# vertical_counter.net
KiCad netlist of a schematic drawn in Altium Designer
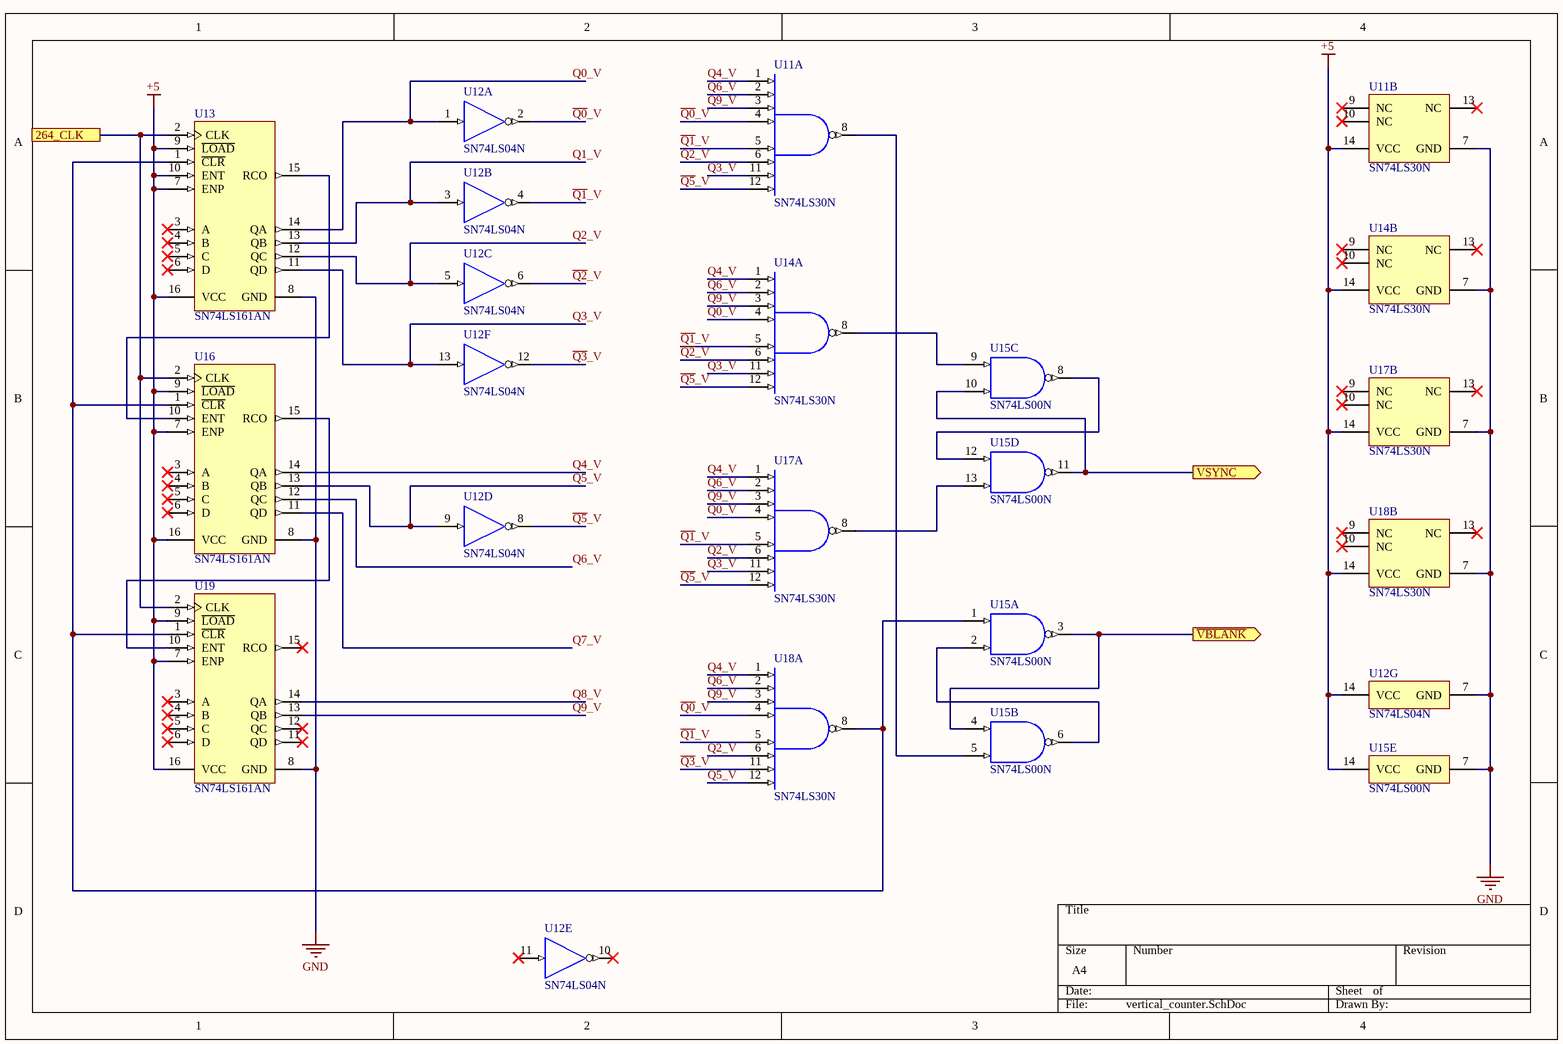
[diagram p0: vertical_counter.SchDoc]

(export (version "E")
  (design (tool "Eeschema 10.0.6"))
  (components
    (comp (ref "U11")
      (value "SN74LS30N")
      (footprint "N0014A")
      (description "8-input positive-NAND gates, N0014A, TUBE")
      (fields
        (field (name "GENERIC PART NUMBER") "SN74LS30")
        (field (name "MANUFACTURER") "Texas Instruments")
      )
      (libsource (lib "Altium Content Vault") (part "TI-SN74XX30-D0014A-14"))
    )
    (comp (ref "U12")
      (value "SN74LS04N")
      (footprint "N0014A")
      (description "Hex inverters, N0014A, TUBE")
      (fields
        (field (name "MANUFACTURER") "Texas Instruments")
        (field (name "GENERIC PART NUMBER") "SN74LS04")
      )
      (libsource (lib "Altium Content Vault") (part "TI-CD_SNX4XXXXXX4X_19A-14"))
    )
    (comp (ref "U13")
      (value "SN74LS161AN")
      (footprint "N0016A")
      (description "Synchronous 4-Bit Binary Counters, N0016A, TUBE")
      (fields
        (field (name "GENERIC PART NUMBER") "SN74LS161A")
        (field (name "MANUFACTURER") "Texas Instruments")
      )
      (libsource (lib "Altium Content Vault") (part "TI-CD_SNX4XXX161_163X-16"))
    )
    (comp (ref "U14")
      (value "SN74LS30N")
      (footprint "N0014A")
      (description "8-input positive-NAND gates, N0014A, TUBE")
      (fields
        (field (name "GENERIC PART NUMBER") "SN74LS30")
        (field (name "MANUFACTURER") "Texas Instruments")
      )
      (libsource (lib "Altium Content Vault") (part "TI-SN74XX30-D0014A-14"))
    )
    (comp (ref "U15")
      (value "SN74LS00N")
      (footprint "N0014A")
      (description "Quad 2-input positive-NAND gates, N0014A, TUBE")
      (fields
        (field (name "MANUFACTURER") "Texas Instruments")
        (field (name "GENERIC PART NUMBER") "SN74LS00")
      )
      (libsource (lib "Altium Content Vault") (part "TI-NAND-4-2IN-14_G"))
    )
    (comp (ref "U16")
      (value "SN74LS161AN")
      (footprint "N0016A")
      (description "Synchronous 4-Bit Binary Counters, N0016A, TUBE")
      (fields
        (field (name "GENERIC PART NUMBER") "SN74LS161A")
        (field (name "MANUFACTURER") "Texas Instruments")
      )
      (libsource (lib "Altium Content Vault") (part "TI-CD_SNX4XXX161_163X-16"))
    )
    (comp (ref "U17")
      (value "SN74LS30N")
      (footprint "N0014A")
      (description "8-input positive-NAND gates, N0014A, TUBE")
      (fields
        (field (name "GENERIC PART NUMBER") "SN74LS30")
        (field (name "MANUFACTURER") "Texas Instruments")
      )
      (libsource (lib "Altium Content Vault") (part "TI-SN74XX30-D0014A-14"))
    )
    (comp (ref "U18")
      (value "SN74LS30N")
      (footprint "N0014A")
      (description "8-input positive-NAND gates, N0014A, TUBE")
      (fields
        (field (name "GENERIC PART NUMBER") "SN74LS30")
        (field (name "MANUFACTURER") "Texas Instruments")
      )
      (libsource (lib "Altium Content Vault") (part "TI-SN74XX30-D0014A-14"))
    )
    (comp (ref "U19")
      (value "SN74LS161AN")
      (footprint "N0016A")
      (description "Synchronous 4-Bit Binary Counters, N0016A, TUBE")
      (fields
        (field (name "GENERIC PART NUMBER") "SN74LS161A")
        (field (name "MANUFACTURER") "Texas Instruments")
      )
      (libsource (lib "Altium Content Vault") (part "TI-CD_SNX4XXX161_163X-16"))
    )
  )
  (nets
    (net (code "1") (name "+5") (class "Default")
      (node (ref "U11") (pin "14") (pinfunction "VCC_14") (pintype "power_in"))
      (node (ref "U12") (pin "14") (pinfunction "VCC_14") (pintype "power_in"))
      (node (ref "U13") (pin "10") (pinfunction "ENT_10") (pintype "input"))
      (node (ref "U13") (pin "16") (pinfunction "VCC_16") (pintype "power_in"))
      (node (ref "U13") (pin "7") (pinfunction "ENP_7") (pintype "input"))
      (node (ref "U13") (pin "9") (pinfunction "~{LOAD}_9") (pintype "input"))
      (node (ref "U14") (pin "14") (pinfunction "VCC_14") (pintype "power_in"))
      (node (ref "U15") (pin "14") (pinfunction "VCC_14") (pintype "power_in"))
      (node (ref "U16") (pin "16") (pinfunction "VCC_16") (pintype "power_in"))
      (node (ref "U16") (pin "7") (pinfunction "ENP_7") (pintype "input"))
      (node (ref "U16") (pin "9") (pinfunction "~{LOAD}_9") (pintype "input"))
      (node (ref "U17") (pin "14") (pinfunction "VCC_14") (pintype "power_in"))
      (node (ref "U18") (pin "14") (pinfunction "VCC_14") (pintype "power_in"))
      (node (ref "U19") (pin "16") (pinfunction "VCC_16") (pintype "power_in"))
      (node (ref "U19") (pin "7") (pinfunction "ENP_7") (pintype "input"))
      (node (ref "U19") (pin "9") (pinfunction "~{LOAD}_9") (pintype "input"))
    )
    (net (code "2") (name "/264_CLK") (class "Default")
      (node (ref "U13") (pin "2") (pinfunction "CLK_2") (pintype "input"))
      (node (ref "U16") (pin "2") (pinfunction "CLK_2") (pintype "input"))
      (node (ref "U19") (pin "2") (pinfunction "CLK_2") (pintype "input"))
    )
    (net (code "3") (name "/Q0_V") (class "Default")
      (node (ref "U12") (pin "1") (pinfunction "1A_1") (pintype "input"))
      (node (ref "U13") (pin "14") (pinfunction "QA_14") (pintype "output"))
      (node (ref "U14") (pin "4") (pinfunction "D_4") (pintype "input"))
      (node (ref "U17") (pin "4") (pinfunction "D_4") (pintype "input"))
    )
    (net (code "4") (name "/Q1_V") (class "Default")
      (node (ref "U12") (pin "3") (pinfunction "2A_3") (pintype "input"))
      (node (ref "U13") (pin "13") (pinfunction "QB_13") (pintype "output"))
    )
    (net (code "5") (name "/Q2_V") (class "Default")
      (node (ref "U12") (pin "5") (pinfunction "3A_5") (pintype "input"))
      (node (ref "U13") (pin "12") (pinfunction "QC_12") (pintype "output"))
      (node (ref "U17") (pin "6") (pinfunction "F_6") (pintype "input"))
      (node (ref "U18") (pin "6") (pinfunction "F_6") (pintype "input"))
    )
    (net (code "6") (name "/Q3_V") (class "Default")
      (node (ref "U11") (pin "11") (pinfunction "G_11") (pintype "input"))
      (node (ref "U12") (pin "13") (pinfunction "6A_13") (pintype "input"))
      (node (ref "U13") (pin "11") (pinfunction "QD_11") (pintype "output"))
      (node (ref "U14") (pin "11") (pinfunction "G_11") (pintype "input"))
      (node (ref "U17") (pin "11") (pinfunction "G_11") (pintype "input"))
    )
    (net (code "7") (name "/Q4_V") (class "Default")
      (node (ref "U11") (pin "1") (pinfunction "A_1") (pintype "input"))
      (node (ref "U14") (pin "1") (pinfunction "A_1") (pintype "input"))
      (node (ref "U16") (pin "14") (pinfunction "QA_14") (pintype "output"))
      (node (ref "U17") (pin "1") (pinfunction "A_1") (pintype "input"))
      (node (ref "U18") (pin "1") (pinfunction "A_1") (pintype "input"))
    )
    (net (code "8") (name "/Q5_V") (class "Default")
      (node (ref "U12") (pin "9") (pinfunction "4A_9") (pintype "input"))
      (node (ref "U16") (pin "13") (pinfunction "QB_13") (pintype "output"))
      (node (ref "U18") (pin "12") (pinfunction "H_12") (pintype "input"))
    )
    (net (code "9") (name "/Q6_V") (class "Default")
      (node (ref "U11") (pin "2") (pinfunction "B_2") (pintype "input"))
      (node (ref "U14") (pin "2") (pinfunction "B_2") (pintype "input"))
      (node (ref "U16") (pin "12") (pinfunction "QC_12") (pintype "output"))
      (node (ref "U17") (pin "2") (pinfunction "B_2") (pintype "input"))
      (node (ref "U18") (pin "2") (pinfunction "B_2") (pintype "input"))
    )
    (net (code "10") (name "/Q7_V") (class "Default")
      (node (ref "U16") (pin "11") (pinfunction "QD_11") (pintype "output"))
    )
    (net (code "11") (name "/Q8_V") (class "Default")
      (node (ref "U19") (pin "14") (pinfunction "QA_14") (pintype "output"))
    )
    (net (code "12") (name "/Q9_V") (class "Default")
      (node (ref "U11") (pin "3") (pinfunction "C_3") (pintype "input"))
      (node (ref "U14") (pin "3") (pinfunction "C_3") (pintype "input"))
      (node (ref "U17") (pin "3") (pinfunction "C_3") (pintype "input"))
      (node (ref "U18") (pin "3") (pinfunction "C_3") (pintype "input"))
      (node (ref "U19") (pin "13") (pinfunction "QB_13") (pintype "output"))
    )
    (net (code "13") (name "/VSYNC") (class "Default")
      (node (ref "U15") (pin "10") (pinfunction "3B_10") (pintype "input"))
      (node (ref "U15") (pin "11") (pinfunction "4Y_11") (pintype "output"))
    )
    (net (code "14") (name "/~{Q0}_V") (class "Default")
      (node (ref "U11") (pin "4") (pinfunction "D_4") (pintype "input"))
      (node (ref "U12") (pin "2") (pinfunction "~{1Y}_2") (pintype "output"))
      (node (ref "U18") (pin "4") (pinfunction "D_4") (pintype "input"))
    )
    (net (code "15") (name "/~{Q1}_V") (class "Default")
      (node (ref "U11") (pin "5") (pinfunction "E_5") (pintype "input"))
      (node (ref "U12") (pin "4") (pinfunction "~{2Y}_4") (pintype "output"))
      (node (ref "U14") (pin "5") (pinfunction "E_5") (pintype "input"))
      (node (ref "U17") (pin "5") (pinfunction "E_5") (pintype "input"))
      (node (ref "U18") (pin "5") (pinfunction "E_5") (pintype "input"))
    )
    (net (code "16") (name "/~{Q2}_V") (class "Default")
      (node (ref "U11") (pin "6") (pinfunction "F_6") (pintype "input"))
      (node (ref "U12") (pin "6") (pinfunction "~{3Y}_6") (pintype "output"))
      (node (ref "U14") (pin "6") (pinfunction "F_6") (pintype "input"))
    )
    (net (code "17") (name "/~{Q3}_V") (class "Default")
      (node (ref "U12") (pin "12") (pinfunction "~{6Y}_12") (pintype "output"))
      (node (ref "U18") (pin "11") (pinfunction "G_11") (pintype "input"))
    )
    (net (code "18") (name "/~{Q5}_V") (class "Default")
      (node (ref "U11") (pin "12") (pinfunction "H_12") (pintype "input"))
      (node (ref "U12") (pin "8") (pinfunction "~{4Y}_8") (pintype "output"))
      (node (ref "U14") (pin "12") (pinfunction "H_12") (pintype "input"))
      (node (ref "U17") (pin "12") (pinfunction "H_12") (pintype "input"))
    )
    (net (code "19") (name "/~{VBLANK}") (class "Default")
      (node (ref "U15") (pin "3") (pinfunction "1Y_3") (pintype "output"))
      (node (ref "U15") (pin "4") (pinfunction "2A_4") (pintype "input"))
    )
    (net (code "20") (name "GND") (class "Default")
      (node (ref "U11") (pin "7") (pinfunction "GND_7") (pintype "power_in"))
      (node (ref "U12") (pin "7") (pinfunction "GND_7") (pintype "power_in"))
      (node (ref "U13") (pin "8") (pinfunction "GND_8") (pintype "power_in"))
      (node (ref "U14") (pin "7") (pinfunction "GND_7") (pintype "power_in"))
      (node (ref "U15") (pin "7") (pinfunction "GND_7") (pintype "power_in"))
      (node (ref "U16") (pin "8") (pinfunction "GND_8") (pintype "power_in"))
      (node (ref "U17") (pin "7") (pinfunction "GND_7") (pintype "power_in"))
      (node (ref "U18") (pin "7") (pinfunction "GND_7") (pintype "power_in"))
      (node (ref "U19") (pin "8") (pinfunction "GND_8") (pintype "power_in"))
    )
    (net (code "21") (name "Net-(U11A-~{Y})") (class "Default")
      (node (ref "U11") (pin "8") (pinfunction "~{Y}_8") (pintype "output"))
      (node (ref "U15") (pin "5") (pinfunction "2B_5") (pintype "input"))
    )
    (net (code "22") (name "Net-(U13-RCO)") (class "Default")
      (node (ref "U13") (pin "15") (pinfunction "RCO_15") (pintype "output"))
      (node (ref "U16") (pin "10") (pinfunction "ENT_10") (pintype "input"))
    )
    (net (code "23") (name "Net-(U13-~{CLR})") (class "Default")
      (node (ref "U13") (pin "1") (pinfunction "~{CLR}_1") (pintype "input"))
      (node (ref "U15") (pin "1") (pinfunction "1A_1") (pintype "input"))
      (node (ref "U16") (pin "1") (pinfunction "~{CLR}_1") (pintype "input"))
      (node (ref "U18") (pin "8") (pinfunction "~{Y}_8") (pintype "output"))
      (node (ref "U19") (pin "1") (pinfunction "~{CLR}_1") (pintype "input"))
    )
    (net (code "24") (name "Net-(U14A-~{Y})") (class "Default")
      (node (ref "U14") (pin "8") (pinfunction "~{Y}_8") (pintype "output"))
      (node (ref "U15") (pin "9") (pinfunction "3A_9") (pintype "input"))
    )
    (net (code "25") (name "Net-(U15A-1B)") (class "Default")
      (node (ref "U15") (pin "2") (pinfunction "1B_2") (pintype "input"))
      (node (ref "U15") (pin "6") (pinfunction "2Y_6") (pintype "output"))
    )
    (net (code "26") (name "Net-(U15C-3Y)") (class "Default")
      (node (ref "U15") (pin "12") (pinfunction "4A_12") (pintype "input"))
      (node (ref "U15") (pin "8") (pinfunction "3Y_8") (pintype "output"))
    )
    (net (code "27") (name "Net-(U15D-4B)") (class "Default")
      (node (ref "U15") (pin "13") (pinfunction "4B_13") (pintype "input"))
      (node (ref "U17") (pin "8") (pinfunction "~{Y}_8") (pintype "output"))
    )
    (net (code "28") (name "Net-(U16-RCO)") (class "Default")
      (node (ref "U16") (pin "15") (pinfunction "RCO_15") (pintype "output"))
      (node (ref "U19") (pin "10") (pinfunction "ENT_10") (pintype "input"))
    )
    (net (code "29") (name "unconnected-(U11B-NC-Pad9)") (class "Default")
      (node (ref "U11") (pin "9") (pinfunction "NC_9") (pintype "passive+no_connect"))
    )
    (net (code "30") (name "unconnected-(U11B-NC-Pad10)") (class "Default")
      (node (ref "U11") (pin "10") (pinfunction "NC_10") (pintype "passive+no_connect"))
    )
    (net (code "31") (name "unconnected-(U11B-NC-Pad13)") (class "Default")
      (node (ref "U11") (pin "13") (pinfunction "NC_13") (pintype "passive+no_connect"))
    )
    (net (code "32") (name "unconnected-(U12E-5A-Pad11)") (class "Default")
      (node (ref "U12") (pin "11") (pinfunction "5A_11") (pintype "input+no_connect"))
    )
    (net (code "33") (name "unconnected-(U12E-~{5Y}-Pad10)") (class "Default")
      (node (ref "U12") (pin "10") (pinfunction "~{5Y}_10") (pintype "output+no_connect"))
    )
    (net (code "34") (name "unconnected-(U13-A-Pad3)") (class "Default")
      (node (ref "U13") (pin "3") (pinfunction "A_3") (pintype "input+no_connect"))
    )
    (net (code "35") (name "unconnected-(U13-B-Pad4)") (class "Default")
      (node (ref "U13") (pin "4") (pinfunction "B_4") (pintype "input+no_connect"))
    )
    (net (code "36") (name "unconnected-(U13-C-Pad5)") (class "Default")
      (node (ref "U13") (pin "5") (pinfunction "C_5") (pintype "input+no_connect"))
    )
    (net (code "37") (name "unconnected-(U13-D-Pad6)") (class "Default")
      (node (ref "U13") (pin "6") (pinfunction "D_6") (pintype "input+no_connect"))
    )
    (net (code "38") (name "unconnected-(U14B-NC-Pad9)") (class "Default")
      (node (ref "U14") (pin "9") (pinfunction "NC_9") (pintype "passive+no_connect"))
    )
    (net (code "39") (name "unconnected-(U14B-NC-Pad10)") (class "Default")
      (node (ref "U14") (pin "10") (pinfunction "NC_10") (pintype "passive+no_connect"))
    )
    (net (code "40") (name "unconnected-(U14B-NC-Pad13)") (class "Default")
      (node (ref "U14") (pin "13") (pinfunction "NC_13") (pintype "passive+no_connect"))
    )
    (net (code "41") (name "unconnected-(U16-A-Pad3)") (class "Default")
      (node (ref "U16") (pin "3") (pinfunction "A_3") (pintype "input+no_connect"))
    )
    (net (code "42") (name "unconnected-(U16-B-Pad4)") (class "Default")
      (node (ref "U16") (pin "4") (pinfunction "B_4") (pintype "input+no_connect"))
    )
    (net (code "43") (name "unconnected-(U16-C-Pad5)") (class "Default")
      (node (ref "U16") (pin "5") (pinfunction "C_5") (pintype "input+no_connect"))
    )
    (net (code "44") (name "unconnected-(U16-D-Pad6)") (class "Default")
      (node (ref "U16") (pin "6") (pinfunction "D_6") (pintype "input+no_connect"))
    )
    (net (code "45") (name "unconnected-(U17B-NC-Pad9)") (class "Default")
      (node (ref "U17") (pin "9") (pinfunction "NC_9") (pintype "passive+no_connect"))
    )
    (net (code "46") (name "unconnected-(U17B-NC-Pad10)") (class "Default")
      (node (ref "U17") (pin "10") (pinfunction "NC_10") (pintype "passive+no_connect"))
    )
    (net (code "47") (name "unconnected-(U17B-NC-Pad13)") (class "Default")
      (node (ref "U17") (pin "13") (pinfunction "NC_13") (pintype "passive+no_connect"))
    )
    (net (code "48") (name "unconnected-(U18B-NC-Pad9)") (class "Default")
      (node (ref "U18") (pin "9") (pinfunction "NC_9") (pintype "passive+no_connect"))
    )
    (net (code "49") (name "unconnected-(U18B-NC-Pad10)") (class "Default")
      (node (ref "U18") (pin "10") (pinfunction "NC_10") (pintype "passive+no_connect"))
    )
    (net (code "50") (name "unconnected-(U18B-NC-Pad13)") (class "Default")
      (node (ref "U18") (pin "13") (pinfunction "NC_13") (pintype "passive+no_connect"))
    )
    (net (code "51") (name "unconnected-(U19-A-Pad3)") (class "Default")
      (node (ref "U19") (pin "3") (pinfunction "A_3") (pintype "input+no_connect"))
    )
    (net (code "52") (name "unconnected-(U19-B-Pad4)") (class "Default")
      (node (ref "U19") (pin "4") (pinfunction "B_4") (pintype "input+no_connect"))
    )
    (net (code "53") (name "unconnected-(U19-C-Pad5)") (class "Default")
      (node (ref "U19") (pin "5") (pinfunction "C_5") (pintype "input+no_connect"))
    )
    (net (code "54") (name "unconnected-(U19-D-Pad6)") (class "Default")
      (node (ref "U19") (pin "6") (pinfunction "D_6") (pintype "input+no_connect"))
    )
    (net (code "55") (name "unconnected-(U19-QC-Pad12)") (class "Default")
      (node (ref "U19") (pin "12") (pinfunction "QC_12") (pintype "output+no_connect"))
    )
    (net (code "56") (name "unconnected-(U19-QD-Pad11)") (class "Default")
      (node (ref "U19") (pin "11") (pinfunction "QD_11") (pintype "output+no_connect"))
    )
    (net (code "57") (name "unconnected-(U19-RCO-Pad15)") (class "Default")
      (node (ref "U19") (pin "15") (pinfunction "RCO_15") (pintype "output+no_connect"))
    )
  )
)
